# PoE_Si3404.net
KiCad netlist of a schematic drawn in Altium Designer
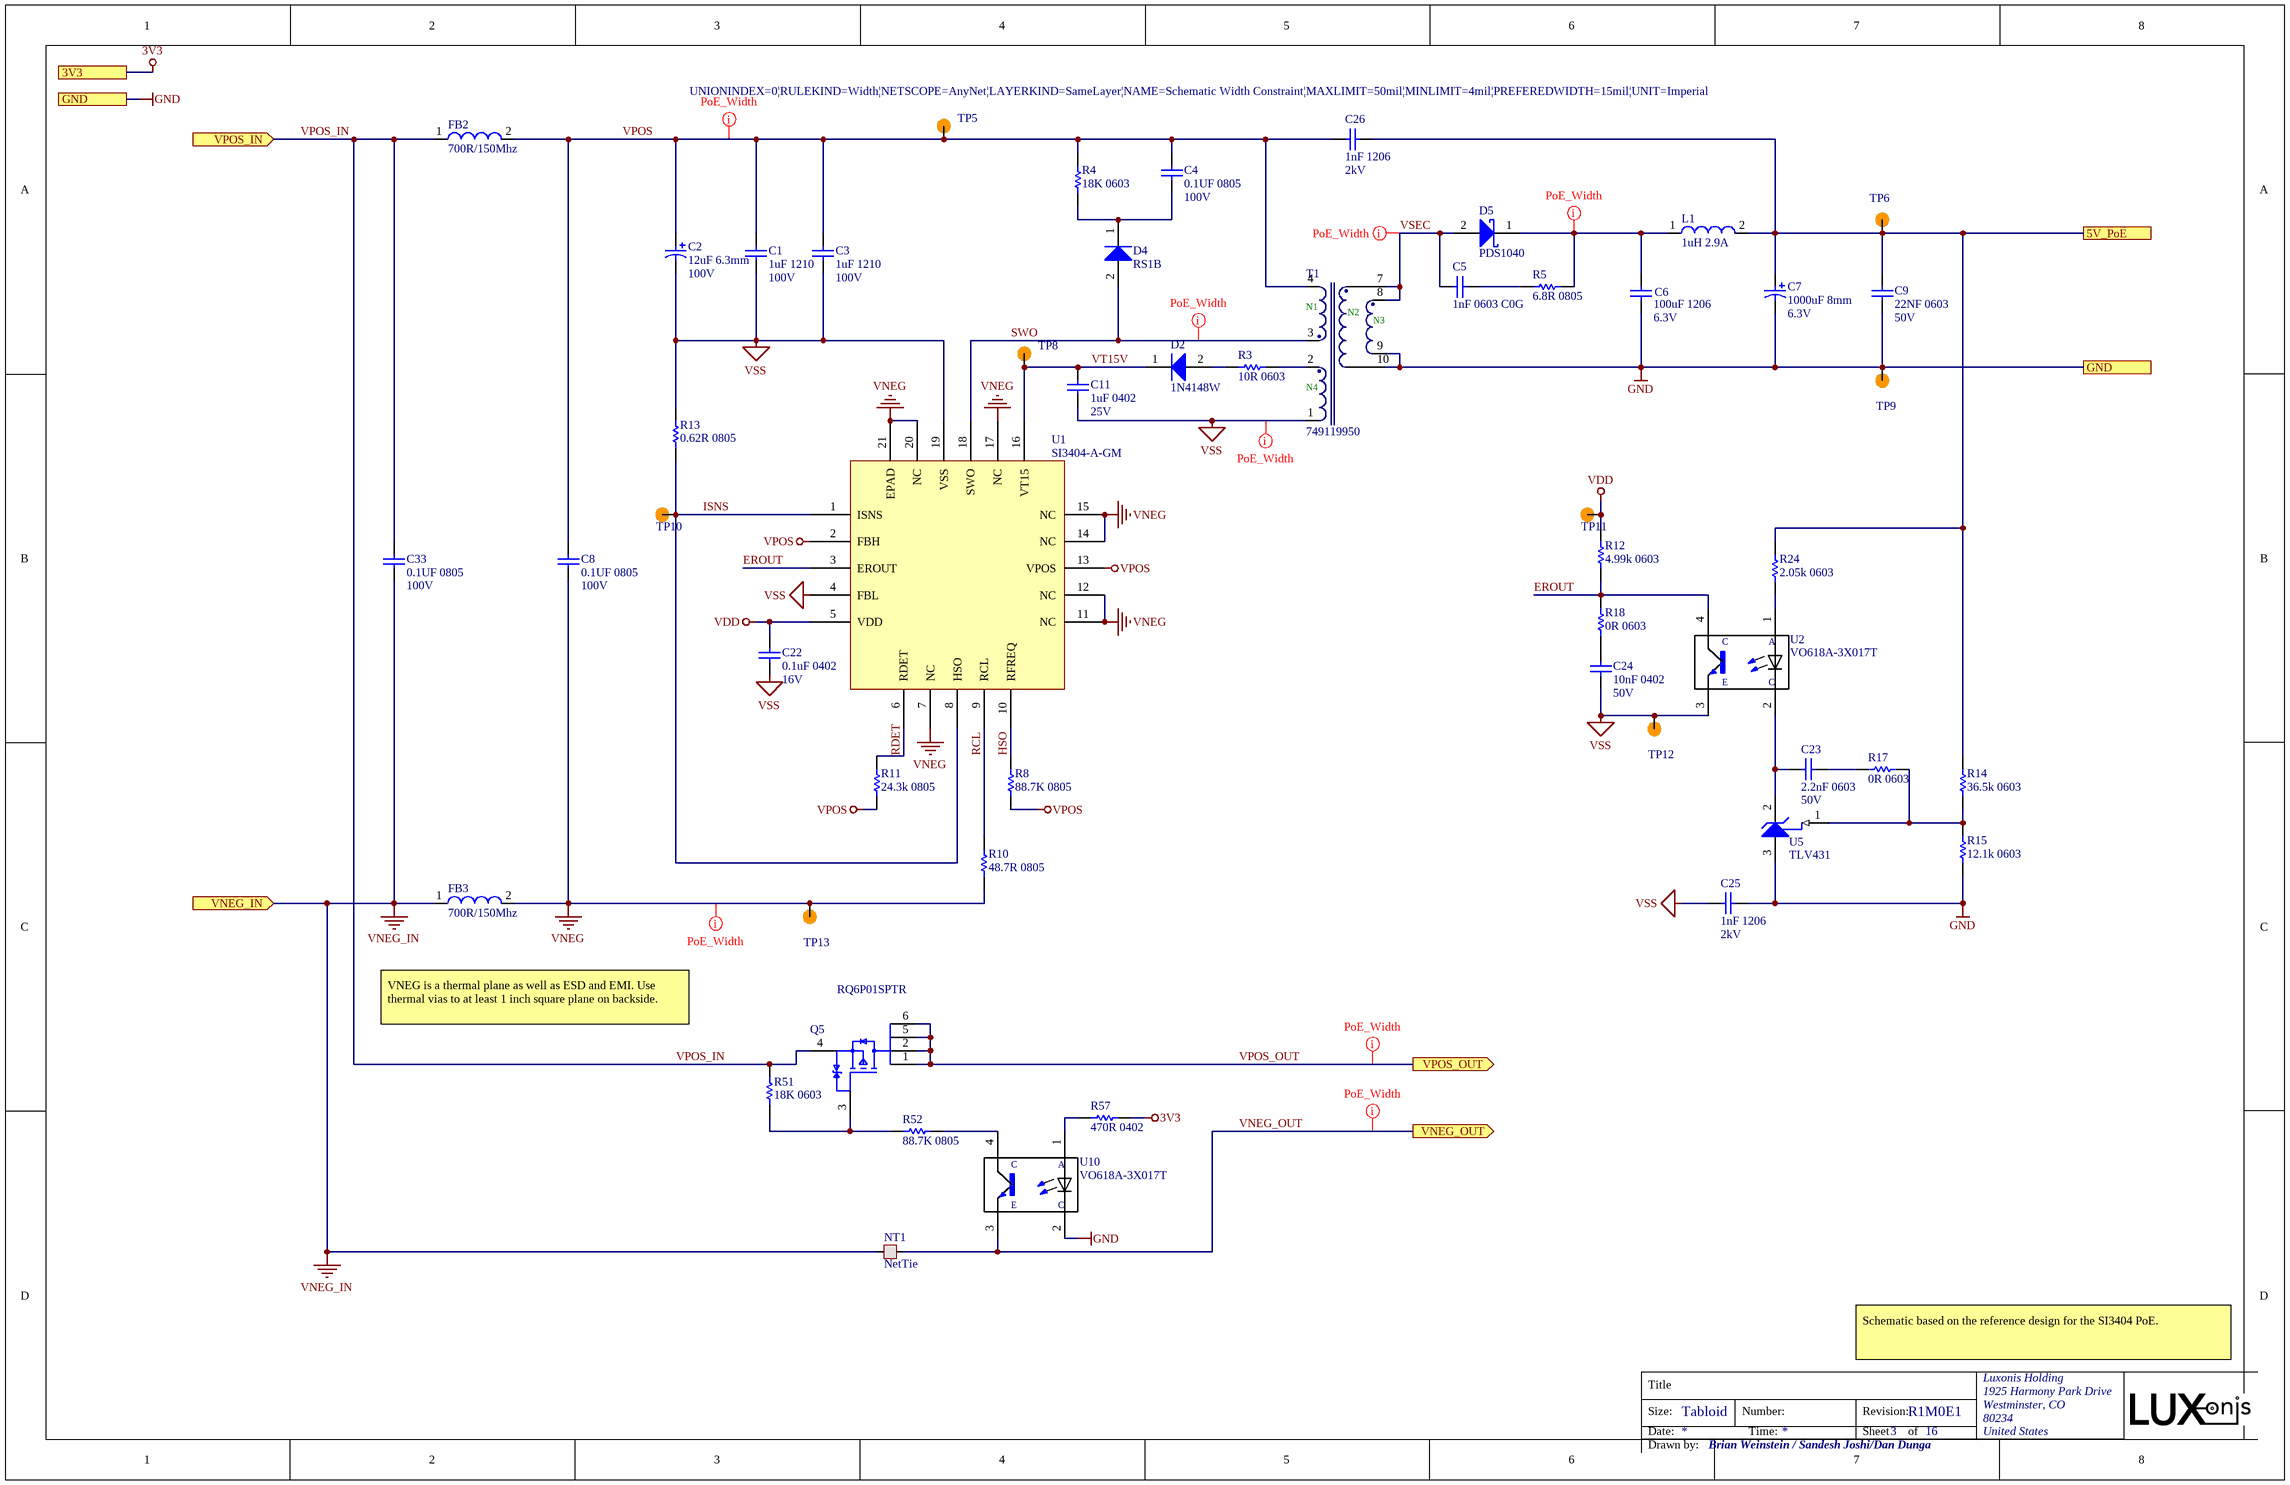
[diagram p0: PoE_Si3404.SchDoc]

(export (version "E")
  (design (tool "Eeschema 10.0.6"))
  (components
    (comp (ref "C1")
      (value "1uF 1210")
      (footprint "CAP_Altium_Vault_Generic:CAPC1210(3225)280_N")
      (description "CAP CER 1UF 100V X7R 1210")
      (fields (field (name "TOLERANCE") "10%") (field (name "VOLTAGE RATING") "100V"))
      (libsource (lib "PCBProject") (part "CL32B105KCJNNNE"))
    )
    (comp (ref "C2")
      (value "12uF 6.3mm")
      (footprint "BW2098POE:EEU-FC2A120")
      (description "CAP ALUM 12UF 20% 100V RADIAL")
      (fields (field (name "TOLERANCE") "20%") (field (name "VOLTAGE") "100V"))
      (libsource (lib "BW2098POE") (part "EEU-FC2A120"))
    )
    (comp (ref "C3")
      (value "1uF 1210")
      (footprint "CAP_Altium_Vault_Generic:CAPC1210(3225)280_N")
      (description "CAP CER 1UF 100V X7R 1210")
      (fields (field (name "TOLERANCE") "10%") (field (name "VOLTAGE RATING") "100V"))
      (libsource (lib "PCBProject") (part "CL32B105KCJNNNE"))
    )
    (comp (ref "C4")
      (value "0.1UF 0805")
      (footprint "CAP_Altium_Vault_Generic:CAPC0805(2012)145_N")
      (description "CAP CER 0.1UF 100V X7R 0805")
      (fields (field (name "TOLERANCE") "10%") (field (name "VOLTAGE RATING") "100V"))
      (libsource (lib "BW2098POE") (part "CL21B104KCFNNNE"))
    )
    (comp (ref "C5")
      (value "1nF 0603 C0G")
      (footprint "CAP_Altium_Vault_Generic:CAPC0603(1608)100_N")
      (description "CAP CER 1000PF 50V C0G/NP0 0603")
      (fields
        (field (name "MANUFACTURER") "Murata")
        (field (name "MANUFACTURER PART NUMBER") "GRM1885C1H102FA01D")
      )
      (libsource (lib "LuxonisMaster") (part "GRM1885C1H102FA01D"))
    )
    (comp (ref "C6")
      (value "100uF 1206")
      (footprint "CAP_Altium_Vault_Generic:CAPC1206(3216)190_N")
      (description "CAP CER 100UF 6.3V X5R 1206")
      (fields (field (name "TOLERANCE") "20%") (field (name "VOLTAGE") "6.3V"))
      (libsource (lib "PCBProject") (part "CL31A107MQHNNNE"))
    )
    (comp (ref "C7")
      (value "1000uF 8mm")
      (footprint "BW2098POE:ECA-0JM102")
      (description "CAP ALUM 1000UF 20% 6.3V RADIAL")
      (fields (field (name "TOLERANCE") "20%") (field (name "VOLTAGE") "6.3V"))
      (libsource (lib "BW2098POE") (part "ECA-0JM102"))
    )
    (comp (ref "C8")
      (value "0.1UF 0805")
      (footprint "CAP_Altium_Vault_Generic:CAPC0805(2012)145_N")
      (description "CAP CER 0.1UF 100V X7R 0805")
      (fields (field (name "TOLERANCE") "10%") (field (name "VOLTAGE RATING") "100V"))
      (libsource (lib "PCBProject") (part "CL21B104KCFNNNE"))
    )
    (comp (ref "C9")
      (value "22NF 0603")
      (footprint "CAP_Altium_Vault_Generic:CAPC0603(1608)100_N")
      (description "CAP CER 0.022UF 50V X7R 0603")
      (fields (field (name "TOLERANCE") "10%") (field (name "VOLTAGE") "50V"))
      (libsource (lib "LuxonisMaster") (part "C0603C223K5RACTU"))
    )
    (comp (ref "C11")
      (value "1uF 0402")
      (footprint "CAP_Altium_Vault_Generic:CAPC0402(1005)70_N")
      (description "CAP CER 1UF 25V X5R 0402 10%")
      (fields
        (field (name "TOLERANCE") "10%")
        (field (name "VOLTAGE") "25V")
        (field (name "VOLTAGE RATING") "25V")
      )
      (libsource (lib "LuxonisMaster") (part "GRM155R61E105KA12D"))
    )
    (comp (ref "C22")
      (value "0.1uF 0402")
      (footprint "CAP_Altium_Vault_Generic:CAPC0402(1005)60_N")
      (description "CAP CER 0.1UF 16V X7R 0402")
      (fields (field (name "TOLERANCE") "10%") (field (name "VOLTAGE RATING") "16V"))
      (libsource (lib "PCBProject") (part "CL05B104KO5NFNC"))
    )
    (comp (ref "C23")
      (value "2.2nF 0603")
      (footprint "CAP_Altium_Vault_Generic:CAPC0603(1608)100_N")
      (description "CAP CER 2200PF 50V C0G/NP0 0603")
      (fields (field (name "TOLERANCE") "5%") (field (name "VOLTAGE") "50V"))
      (libsource (lib "BW2098POE") (part "GRM1885C1H222JA01D"))
    )
    (comp (ref "C24")
      (value "10nF 0402")
      (footprint "CAP_Altium_Vault_Generic:CAPC0402(1005)60_N")
      (description "CAP CER 10000PF 50V X7R 0402")
      (fields
        (field (name "TOLERANCE") "10%")
        (field (name "VOLTAGE") "25V")
        (field (name "VOLTAGE RATING") "50V")
      )
      (libsource (lib "LuxonisMaster") (part "GRM155R71H103KA88D"))
    )
    (comp (ref "C25")
      (value "1nF 1206")
      (footprint "CAP_Altium_Vault_Generic:CAPC1206(3216)190_N")
      (description "CAP CER 1000PF 2KV X7R 1206")
      (fields (field (name "TOLERANCE") "10%") (field (name "VOLTAGE RATING (DC)") "2kV"))
      (libsource (lib "PCBProject") (part "C1206C102KGRACTU"))
    )
    (comp (ref "C26")
      (value "1nF 1206")
      (footprint "CAP_Altium_Vault_Generic:CAPC1206(3216)190_N")
      (description "CAP CER 1000PF 2KV X7R 1206")
      (fields (field (name "TOLERANCE") "10%") (field (name "VOLTAGE RATING (DC)") "2kV"))
      (libsource (lib "PCBProject") (part "C1206C102KGRACTU"))
    )
    (comp (ref "C33")
      (value "0.1UF 0805")
      (footprint "CAP_Altium_Vault_Generic:CAPC0805(2012)145_N")
      (description "CAP CER 0.1UF 100V X7R 0805")
      (fields (field (name "TOLERANCE") "10%") (field (name "VOLTAGE RATING") "100V"))
      (libsource (lib "PCBProject") (part "CL21B104KCFNNNE"))
    )
    (comp (ref "D2")
      (value "1N4148W")
      (footprint "BW2098POE:1N4148W-7-F")
      (description "DIODE GEN PURP 100V 300MA SOD123")
      (fields (field (name "VOLTAGE") "100V"))
      (libsource (lib "PCBProject") (part "1N4148W-7-F"))
    )
    (comp (ref "D4")
      (value "RS1B")
      (footprint "BW2098POE:RS1B")
      (description "DIODE GEN PURP 100V 1A SMA")
      (libsource (lib "BW2098POE") (part "RS1B"))
    )
    (comp (ref "D5")
      (value "PDS1040")
      (footprint "BW2098POE:PDS1040-13")
      (description "DIODE SCHOTTKY 40V 10A POWERDI5")
      (libsource (lib "PCBProject") (part "PDS1040-13"))
    )
    (comp (ref "FB2")
      (value "700R/150Mhz")
      (footprint "BW2098POE:742792040")
      (description "FERRITE BEAD 600 OHM 0805 1LN")
      (fields (field (name "TOLERANCE") "25%"))
      (libsource (lib "BW2098POE") (part "742792040"))
    )
    (comp (ref "FB3")
      (value "700R/150Mhz")
      (footprint "BW2098POE:742792040")
      (description "FERRITE BEAD 600 OHM 0805 1LN")
      (fields (field (name "TOLERANCE") "25%"))
      (libsource (lib "BW2098POE") (part "742792040"))
    )
    (comp (ref "L1")
      (value "1uH 2.9A")
      (footprint "BW2098POE:DO1608C-102MLx")
      (description "IND POWER WIREWOUND 1uH 20% 100KHz FERRITE 2.7A")
      (fields (field (name "TOLERANCE") "20%"))
      (libsource (lib "PCBProject") (part "DO1608C-102ML"))
    )
    (comp (ref "NT1")
      (value "NetTie")
      (footprint "NET_TIE_TOP_1mm")
      (description "Net tie Top/Bottom layer")
      (libsource (lib "BW2098POE_Anfa") (part "Net_Tie"))
    )
    (comp (ref "Q5")
      (value "RQ6P01SPTR")
      (footprint "RQ6P015SPTR")
      (description "P Channel Mosfet -100V -1.5A")
      (libsource (lib "AR8327N-AL1A") (part "RQ6P01SPTR"))
    )
    (comp (ref "R3")
      (value "10R 0603")
      (footprint "RESC0603(1608)_N")
      (description "RES SMD 10 OHM 1% 1/10W 0603")
      (fields (field (name "TOLERANCE") "1%"))
      (libsource (lib "PCBProject") (part "CRCW060310R0FKEA"))
    )
    (comp (ref "R4")
      (value "18K 0603")
      (footprint "RESC0603(1608)_N")
      (description "RES SMD 18K OHM 5% 1/10W 0603")
      (fields (field (name "TOLERANCE") "5%"))
      (libsource (lib "BW2098POE") (part "RC0603JR-0718KL"))
    )
    (comp (ref "R5")
      (value "6.8R 0805")
      (footprint "RES_Altium_Vault_Generic:RESC0805(2012)_N")
      (description "RES SMD 6.8 OHM 1% 1/8W 0805")
      (fields (field (name "TOLERANCE") "1%"))
      (libsource (lib "BW2098POE") (part "RC0805FR-076R8L"))
    )
    (comp (ref "R8")
      (value "88.7K 0805")
      (footprint "RES_Altium_Vault_Generic:RESC0805(2012)_N")
      (description "RES SMD 88.7K OHM 1% 1/8W 0805")
      (fields (field (name "TOLERANCE") "1%"))
      (libsource (lib "BW2098POE") (part "CRCW080588K7FKEA"))
    )
    (comp (ref "R10")
      (value "48.7R 0805")
      (footprint "RES_Altium_Vault_Generic:RESC0805(2012)_N")
      (description "RES SMD 48.7 OHM 1% 1/8W 0805")
      (fields (field (name "TOLERANCE") "1%"))
      (libsource (lib "PCBProject") (part "RC0805FR-0748R7L"))
    )
    (comp (ref "R11")
      (value "24.3k 0805")
      (footprint "RES_Altium_Vault_Generic:RESC0805(2012)_N")
      (description "RES SMD 24.3K OHM 1% 1/8W 0805")
      (fields (field (name "TOLERANCE") "1%"))
      (libsource (lib "PCBProject") (part "CRCW080524K3FKEA"))
    )
    (comp (ref "R12")
      (value "4.99k 0603")
      (footprint "RESC0603(1608)_N")
      (description "RES SMD 4.99K OHM 1% 1/10W 0603")
      (fields (field (name "TOLERANCE") "1%"))
      (libsource (lib "PCBProject") (part "RC0603FR-074K99L"))
    )
    (comp (ref "R13")
      (value "0.62R 0805")
      (footprint "RES_Altium_Vault_Generic:RESC0805(2012)_N")
      (description "RES SMD 620 MOHM 1% 1/8W 0805")
      (fields (field (name "TOLERANCE") "1%"))
      (libsource (lib "BW2098POE") (part "RL0805FR-070R62L"))
    )
    (comp (ref "R14")
      (value "36.5k 0603")
      (footprint "RESC0603(1608)_N")
      (description "RES SMD 36.5K OHM 1% 1/10W 0603")
      (fields (field (name "TOLERANCE") "1%"))
      (libsource (lib "PCBProject") (part "RC0603FR-0736K5L"))
    )
    (comp (ref "R15")
      (value "12.1k 0603")
      (footprint "RESC0603(1608)_N")
      (description "RES SMD 12.1K OHM 1% 1/10W 0603")
      (fields (field (name "TOLERANCE") "1%"))
      (libsource (lib "PCBProject") (part "RC0603FR-0712K1L"))
    )
    (comp (ref "R17")
      (value "0R 0603")
      (footprint "RESC0603(1608)_N")
      (fields (field (name "TOLERANCE") "5%"))
      (libsource (lib "LuxonisMaster") (part "CRCW06030000Z0EA"))
    )
    (comp (ref "R18")
      (value "0R 0603")
      (footprint "RESC0603(1608)_N")
      (fields (field (name "TOLERANCE") "5%"))
      (libsource (lib "LuxonisMaster") (part "CRCW06030000Z0EA"))
    )
    (comp (ref "R24")
      (value "2.05k 0603")
      (footprint "RESC0603(1608)_N")
      (description "RES SMD 2.05K OHM 1% 1/10W 0603")
      (fields (field (name "TOLERANCE") "1%"))
      (libsource (lib "PCBProject") (part "RC0603FR-072K05L"))
    )
    (comp (ref "R51")
      (value "18K 0603")
      (footprint "RESC0603(1608)_N")
      (description "RES SMD 18K OHM 5% 1/10W 0603")
      (fields (field (name "TOLERANCE") "5%"))
      (libsource (lib "BW2098POE") (part "RC0603JR-0718KL"))
    )
    (comp (ref "R52")
      (value "88.7K 0805")
      (footprint "RESC0805(2012)_N")
      (description "RES SMD 88.7K OHM 1% 1/8W 0805")
      (fields (field (name "TOLERANCE") "1%"))
      (libsource (lib "BW2098POE") (part "CRCW080588K7FKEA"))
    )
    (comp (ref "R57")
      (value "470R 0402")
      (footprint "RESC0402(1005)_N")
      (description "RES SMD 470 OHM 1% 1/16W 0402")
      (fields (field (name "TOLERANCE") "1%"))
      (libsource (lib "LuxonisMaster") (part "CRCW0402470RFKED"))
    )
    (comp (ref "T1")
      (value "749119950")
      (footprint "BW2098POE:749119950")
      (description "TRANS FLYBACK POE 127UH SMD")
      (libsource (lib "BW2098POE") (part "749119950"))
    )
    (comp (ref "TP5")
      (value "TP100_200_NS")
      (footprint "TP100_200_NS")
      (libsource (lib "LuxonisMaster") (part "TEST_POINT"))
    )
    (comp (ref "TP6")
      (value "TP100_200_NS")
      (footprint "TP100_200_NS")
      (libsource (lib "LuxonisMaster") (part "TEST_POINT"))
    )
    (comp (ref "TP8")
      (value "TP100_200_NS")
      (footprint "TP100_200_NS")
      (libsource (lib "LuxonisMaster") (part "TEST_POINT"))
    )
    (comp (ref "TP9")
      (value "TP100_200_NS")
      (footprint "TP100_200_NS")
      (libsource (lib "LuxonisMaster") (part "TEST_POINT"))
    )
    (comp (ref "TP10")
      (value "TP100_200_NS")
      (footprint "TP100_200_NS")
      (libsource (lib "LuxonisMaster") (part "TEST_POINT"))
    )
    (comp (ref "TP11")
      (value "TP100_200_NS")
      (footprint "TP100_200_NS")
      (libsource (lib "LuxonisMaster") (part "TEST_POINT"))
    )
    (comp (ref "TP12")
      (value "TP100_200_NS")
      (footprint "TP100_200_NS")
      (libsource (lib "LuxonisMaster") (part "TEST_POINT"))
    )
    (comp (ref "TP13")
      (value "TP100_200_NS")
      (footprint "TP100_200_NS")
      (libsource (lib "LuxonisMaster") (part "TEST_POINT"))
    )
    (comp (ref "U1")
      (value "SI3404-A-GM")
      (footprint "BW2098POE:Si3404-A-GM")
      (description "IC POE CNTRL 1 CHANNEL 20QFN")
      (libsource (lib "BW2098POE") (part "SI3404-A-GM"))
    )
    (comp (ref "U2")
      (value "VO618A-3X017T")
      (footprint "BW2098POE:VO618A-3X017T")
      (description "OPTOISOLATOR 5.3KV TRANS 4-SMD")
      (libsource (lib "BW2098POE") (part "VO618A-3X017T"))
    )
    (comp (ref "U5")
      (value "TLV431")
      (footprint "BW2098POE:TLV431BCDBZR")
      (description "IC VREF SHUNT ADJ SOT23-3")
      (fields (field (name "TOLERANCE") "0.5%"))
      (libsource (lib "BW2098POE") (part "TLV431BCDBZR"))
    )
    (comp (ref "U10")
      (value "VO618A-3X017T")
      (footprint "VO618A-3X017T")
      (description "OPTOISOLATOR 5.3KV TRANS 4-SMD")
      (libsource (lib "BW2098POE") (part "VO618A-3X017T"))
    )
  )
  (nets
    (net (code "1") (name "/5V_PoE") (class "Default")
      (node (ref "C26") (pin "2") (pinfunction "2_2") (pintype "passive"))
      (node (ref "C7") (pin "1") (pinfunction "1_1") (pintype "passive"))
      (node (ref "C9") (pin "2") (pinfunction "2_2") (pintype "passive"))
      (node (ref "L1") (pin "2") (pinfunction "2_2") (pintype "passive"))
      (node (ref "R14") (pin "2") (pinfunction "2_2") (pintype "passive"))
      (node (ref "R24") (pin "2") (pinfunction "2_2") (pintype "passive"))
      (node (ref "TP6") (pin "1") (pintype "passive"))
    )
    (net (code "2") (name "/EROUT") (class "Default")
      (node (ref "R12") (pin "1") (pinfunction "1_1") (pintype "passive"))
      (node (ref "R18") (pin "2") (pinfunction "2_2") (pintype "passive"))
      (node (ref "U1") (pin "3") (pinfunction "EROUT_3") (pintype "passive"))
      (node (ref "U2") (pin "4") (pinfunction "CO_4") (pintype "passive"))
    )
    (net (code "3") (name "/HSO") (class "Default")
      (node (ref "R8") (pin "2") (pinfunction "2_2") (pintype "passive"))
      (node (ref "U1") (pin "10") (pinfunction "RFREQ_10") (pintype "passive"))
    )
    (net (code "4") (name "/ISNS") (class "Default")
      (node (ref "R13") (pin "1") (pinfunction "1_1") (pintype "passive"))
      (node (ref "TP10") (pin "1") (pintype "passive"))
      (node (ref "U1") (pin "1") (pinfunction "ISNS_1") (pintype "passive"))
      (node (ref "U1") (pin "8") (pinfunction "HSO_8") (pintype "passive"))
    )
    (net (code "5") (name "/RCL") (class "Default")
      (node (ref "R10") (pin "2") (pinfunction "2_2") (pintype "passive"))
      (node (ref "U1") (pin "9") (pinfunction "RCL_9") (pintype "passive"))
    )
    (net (code "6") (name "/RDET") (class "Default")
      (node (ref "R11") (pin "2") (pinfunction "2_2") (pintype "passive"))
      (node (ref "U1") (pin "6") (pinfunction "RDET_6") (pintype "passive"))
    )
    (net (code "7") (name "/SWO") (class "Default")
      (node (ref "D4") (pin "2") (pinfunction "A_2") (pintype "passive"))
      (node (ref "T1") (pin "3") (pinfunction "3_3") (pintype "passive"))
      (node (ref "U1") (pin "18") (pinfunction "SWO_18") (pintype "passive"))
    )
    (net (code "8") (name "/VNEG_OUT") (class "Default")
      (node (ref "NT1") (pin "2") (pinfunction "2_2") (pintype "passive"))
      (node (ref "U10") (pin "3") (pinfunction "E_3") (pintype "passive"))
    )
    (net (code "9") (name "/VPOS_IN") (class "Default")
      (node (ref "C33") (pin "2") (pinfunction "2_2") (pintype "passive"))
      (node (ref "FB2") (pin "1") (pinfunction "1_1") (pintype "passive"))
      (node (ref "Q5") (pin "4") (pinfunction "Source_4") (pintype "passive"))
      (node (ref "R51") (pin "1") (pinfunction "1_1") (pintype "passive"))
    )
    (net (code "10") (name "/VPOS_OUT") (class "Default")
      (node (ref "Q5") (pin "1") (pinfunction "Drain_1") (pintype "passive"))
      (node (ref "Q5") (pin "2") (pinfunction "Drain_2") (pintype "passive"))
      (node (ref "Q5") (pin "5") (pinfunction "Drain_5") (pintype "passive"))
      (node (ref "Q5") (pin "6") (pinfunction "Drain_6") (pintype "passive"))
    )
    (net (code "11") (name "/VSEC") (class "Default")
      (node (ref "C5") (pin "2") (pinfunction "2_2") (pintype "passive"))
      (node (ref "D5") (pin "2") (pinfunction "A_2") (pintype "passive"))
      (node (ref "T1") (pin "7") (pinfunction "7_7") (pintype "passive"))
      (node (ref "T1") (pin "8") (pinfunction "8_8") (pintype "passive"))
    )
    (net (code "12") (name "/VT15V") (class "Default")
      (node (ref "C11") (pin "2") (pinfunction "2_2") (pintype "passive"))
      (node (ref "D2") (pin "1") (pinfunction "K_1") (pintype "passive"))
      (node (ref "TP8") (pin "1") (pintype "passive"))
      (node (ref "U1") (pin "16") (pinfunction "VT15_16") (pintype "passive"))
    )
    (net (code "13") (name "3V3") (class "Default")
      (node (ref "R57") (pin "2") (pinfunction "2_2") (pintype "passive"))
    )
    (net (code "14") (name "GND") (class "Default")
      (node (ref "C25") (pin "2") (pinfunction "2_2") (pintype "passive"))
      (node (ref "C6") (pin "1") (pinfunction "1_1") (pintype "passive"))
      (node (ref "C7") (pin "2") (pinfunction "2_2") (pintype "passive"))
      (node (ref "C9") (pin "1") (pinfunction "1_1") (pintype "passive"))
      (node (ref "R15") (pin "1") (pinfunction "1_1") (pintype "passive"))
      (node (ref "T1") (pin "10") (pinfunction "10_10") (pintype "passive"))
      (node (ref "T1") (pin "9") (pinfunction "9_9") (pintype "passive"))
      (node (ref "TP9") (pin "1") (pintype "passive"))
      (node (ref "U10") (pin "2") (pinfunction "C_2") (pintype "passive"))
      (node (ref "U5") (pin "3") (pinfunction "ANODE_3") (pintype "passive"))
    )
    (net (code "15") (name "Net-(C5-Pad1)") (class "Default")
      (node (ref "C5") (pin "1") (pinfunction "1_1") (pintype "passive"))
      (node (ref "R5") (pin "1") (pinfunction "1_1") (pintype "passive"))
    )
    (net (code "16") (name "Net-(C23-Pad2)") (class "Default")
      (node (ref "C23") (pin "2") (pinfunction "2_2") (pintype "passive"))
      (node (ref "R17") (pin "2") (pinfunction "2_2") (pintype "passive"))
    )
    (net (code "17") (name "Net-(C24-Pad2)") (class "Default")
      (node (ref "C24") (pin "2") (pinfunction "2_2") (pintype "passive"))
      (node (ref "R18") (pin "1") (pinfunction "1_1") (pintype "passive"))
    )
    (net (code "18") (name "Net-(D2-A)") (class "Default")
      (node (ref "D2") (pin "2") (pinfunction "A_2") (pintype "passive"))
      (node (ref "R3") (pin "1") (pinfunction "1_1") (pintype "passive"))
    )
    (net (code "19") (name "Net-(D4-K)") (class "Default")
      (node (ref "C4") (pin "1") (pinfunction "1_1") (pintype "passive"))
      (node (ref "D4") (pin "1") (pinfunction "K_1") (pintype "passive"))
      (node (ref "R4") (pin "1") (pinfunction "1_1") (pintype "passive"))
    )
    (net (code "20") (name "Net-(D5-K)") (class "Default")
      (node (ref "C6") (pin "2") (pinfunction "2_2") (pintype "passive"))
      (node (ref "D5") (pin "1") (pinfunction "K_1") (pintype "passive"))
      (node (ref "L1") (pin "1") (pinfunction "1_1") (pintype "passive"))
      (node (ref "R5") (pin "2") (pinfunction "2_2") (pintype "passive"))
    )
    (net (code "21") (name "Net-(Q5-Gate)") (class "Default")
      (node (ref "Q5") (pin "3") (pinfunction "Gate_3") (pintype "passive"))
      (node (ref "R51") (pin "2") (pinfunction "2_2") (pintype "passive"))
      (node (ref "R52") (pin "2") (pinfunction "2_2") (pintype "passive"))
    )
    (net (code "22") (name "Net-(R3-Pad2)") (class "Default")
      (node (ref "R3") (pin "2") (pinfunction "2_2") (pintype "passive"))
      (node (ref "T1") (pin "2") (pinfunction "2_2") (pintype "passive"))
    )
    (net (code "23") (name "Net-(U2-A)") (class "Default")
      (node (ref "R24") (pin "1") (pinfunction "1_1") (pintype "passive"))
      (node (ref "U2") (pin "1") (pinfunction "A_1") (pintype "passive"))
    )
    (net (code "24") (name "Net-(U2-C)") (class "Default")
      (node (ref "C23") (pin "1") (pinfunction "1_1") (pintype "passive"))
      (node (ref "U2") (pin "2") (pinfunction "C_2") (pintype "passive"))
      (node (ref "U5") (pin "2") (pinfunction "CATHODE_2") (pintype "passive"))
    )
    (net (code "25") (name "Net-(U5-REF)") (class "Default")
      (node (ref "R14") (pin "1") (pinfunction "1_1") (pintype "passive"))
      (node (ref "R15") (pin "2") (pinfunction "2_2") (pintype "passive"))
      (node (ref "R17") (pin "1") (pinfunction "1_1") (pintype "passive"))
      (node (ref "U5") (pin "1") (pinfunction "REF_1") (pintype "input"))
    )
    (net (code "26") (name "Net-(U10-A)") (class "Default")
      (node (ref "R57") (pin "1") (pinfunction "1_1") (pintype "passive"))
      (node (ref "U10") (pin "1") (pinfunction "A_1") (pintype "passive"))
    )
    (net (code "27") (name "Net-(U10-CO)") (class "Default")
      (node (ref "R52") (pin "1") (pinfunction "1_1") (pintype "passive"))
      (node (ref "U10") (pin "4") (pinfunction "CO_4") (pintype "passive"))
    )
    (net (code "28") (name "VDD") (class "Default")
      (node (ref "C22") (pin "2") (pinfunction "2_2") (pintype "passive"))
      (node (ref "R12") (pin "2") (pinfunction "2_2") (pintype "passive"))
      (node (ref "TP11") (pin "1") (pintype "passive"))
      (node (ref "U1") (pin "5") (pinfunction "VDD_5") (pintype "passive"))
    )
    (net (code "29") (name "VNEG") (class "Default")
      (node (ref "C8") (pin "1") (pinfunction "1_1") (pintype "passive"))
      (node (ref "FB3") (pin "2") (pinfunction "2_2") (pintype "passive"))
      (node (ref "R10") (pin "1") (pinfunction "1_1") (pintype "passive"))
      (node (ref "TP13") (pin "1") (pintype "passive"))
      (node (ref "U1") (pin "11") (pinfunction "NC_11") (pintype "passive"))
      (node (ref "U1") (pin "12") (pinfunction "NC_12") (pintype "passive"))
      (node (ref "U1") (pin "14") (pinfunction "NC_14") (pintype "passive"))
      (node (ref "U1") (pin "15") (pinfunction "NC_15") (pintype "passive"))
      (node (ref "U1") (pin "17") (pinfunction "NC_17") (pintype "passive"))
      (node (ref "U1") (pin "20") (pinfunction "NC_20") (pintype "passive"))
      (node (ref "U1") (pin "21") (pinfunction "EPAD_21") (pintype "passive"))
      (node (ref "U1") (pin "7") (pinfunction "NC_7") (pintype "passive"))
    )
    (net (code "30") (name "VNEG_IN") (class "Default")
      (node (ref "C33") (pin "1") (pinfunction "1_1") (pintype "passive"))
      (node (ref "FB3") (pin "1") (pinfunction "1_1") (pintype "passive"))
      (node (ref "NT1") (pin "1") (pinfunction "1_1") (pintype "passive"))
    )
    (net (code "31") (name "VPOS") (class "Default")
      (node (ref "C1") (pin "2") (pinfunction "2_2") (pintype "passive"))
      (node (ref "C2") (pin "1") (pinfunction "1_1") (pintype "passive"))
      (node (ref "C26") (pin "1") (pinfunction "1_1") (pintype "passive"))
      (node (ref "C3") (pin "2") (pinfunction "2_2") (pintype "passive"))
      (node (ref "C4") (pin "2") (pinfunction "2_2") (pintype "passive"))
      (node (ref "C8") (pin "2") (pinfunction "2_2") (pintype "passive"))
      (node (ref "FB2") (pin "2") (pinfunction "2_2") (pintype "passive"))
      (node (ref "R11") (pin "1") (pinfunction "1_1") (pintype "passive"))
      (node (ref "R4") (pin "2") (pinfunction "2_2") (pintype "passive"))
      (node (ref "R8") (pin "1") (pinfunction "1_1") (pintype "passive"))
      (node (ref "T1") (pin "4") (pinfunction "4_4") (pintype "passive"))
      (node (ref "TP5") (pin "1") (pintype "passive"))
      (node (ref "U1") (pin "13") (pinfunction "VPOS_13") (pintype "passive"))
      (node (ref "U1") (pin "2") (pinfunction "FBH_2") (pintype "passive"))
    )
    (net (code "32") (name "VSS") (class "Default")
      (node (ref "C1") (pin "1") (pinfunction "1_1") (pintype "passive"))
      (node (ref "C11") (pin "1") (pinfunction "1_1") (pintype "passive"))
      (node (ref "C2") (pin "2") (pinfunction "2_2") (pintype "passive"))
      (node (ref "C22") (pin "1") (pinfunction "1_1") (pintype "passive"))
      (node (ref "C24") (pin "1") (pinfunction "1_1") (pintype "passive"))
      (node (ref "C25") (pin "1") (pinfunction "1_1") (pintype "passive"))
      (node (ref "C3") (pin "1") (pinfunction "1_1") (pintype "passive"))
      (node (ref "R13") (pin "2") (pinfunction "2_2") (pintype "passive"))
      (node (ref "T1") (pin "1") (pinfunction "1_1") (pintype "passive"))
      (node (ref "TP12") (pin "1") (pintype "passive"))
      (node (ref "U1") (pin "19") (pinfunction "VSS_19") (pintype "passive"))
      (node (ref "U1") (pin "4") (pinfunction "FBL_4") (pintype "passive"))
      (node (ref "U2") (pin "3") (pinfunction "E_3") (pintype "passive"))
    )
  )
)
